# Adafruit_BME280.net
KiCad netlist of a schematic drawn in EAGLE
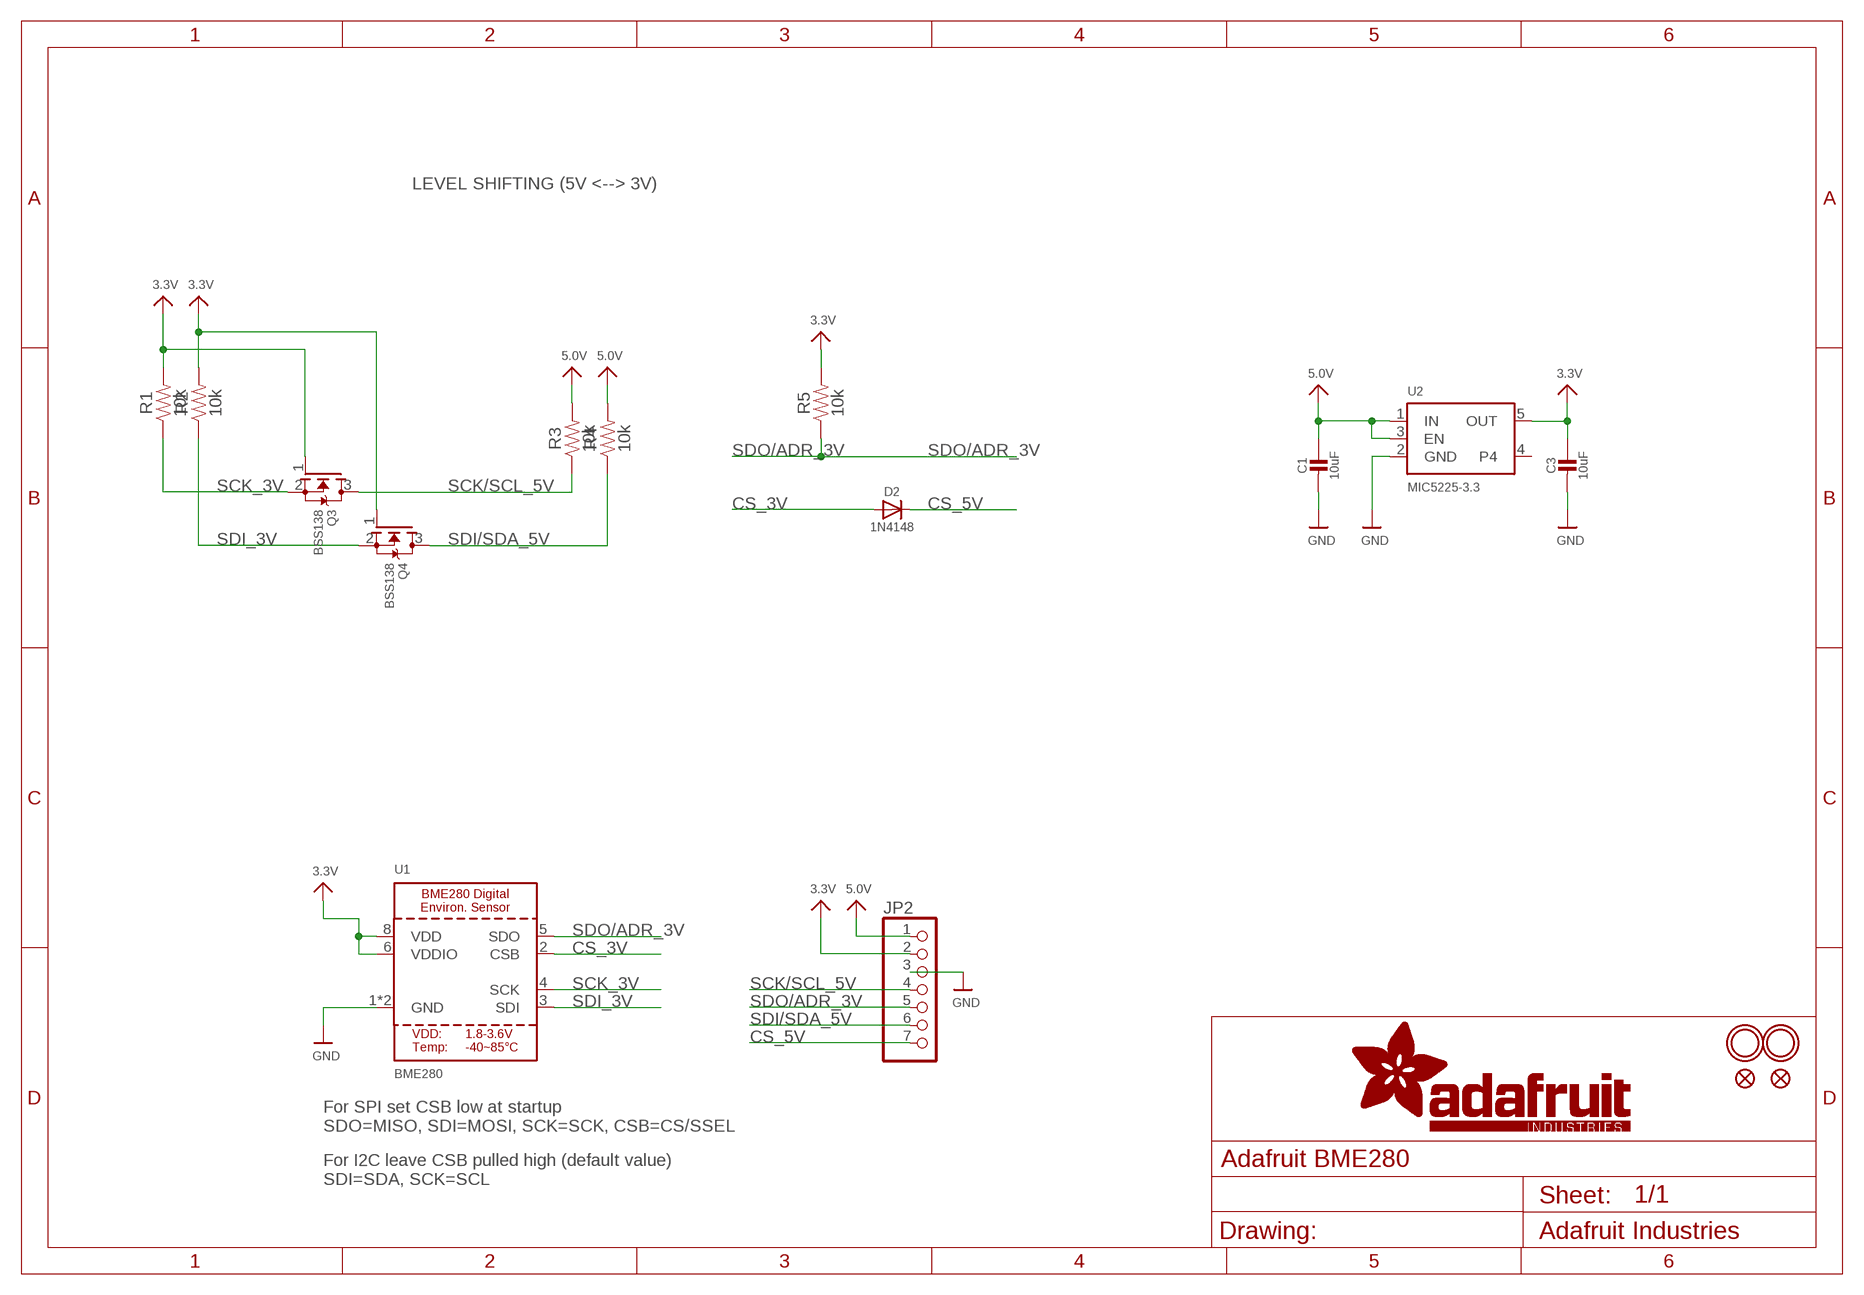
[diagram p0: schematic, sheet 1]

(export (version "E")
  (design (tool "Eeschema 10.0.6"))
  (components
    (comp (ref "C1")
      (value "10uF")
      (footprint "eagle-import:0805-NO")
      (libsource (lib "eagle-import") (part "CAP_CERAMIC0805-NOOUTLINE"))
    )
    (comp (ref "C3")
      (value "10uF")
      (footprint "eagle-import:0805-NO")
      (libsource (lib "eagle-import") (part "CAP_CERAMIC0805-NOOUTLINE"))
    )
    (comp (ref "D2")
      (value "1N4148")
      (footprint "eagle-import:SOD-323")
      (libsource (lib "eagle-import") (part "DIODESOD-323"))
    )
    (comp (ref "JP2")
      (value "HEADER-1X770MIL")
      (footprint "eagle-import:1X07_ROUND_70")
      (libsource (lib "eagle-import") (part "HEADER-1X770MIL"))
    )
    (comp (ref "Q3")
      (value "BSS138")
      (footprint "eagle-import:SOT23-WIDE")
      (libsource (lib "eagle-import") (part "MOSFET-NWIDE"))
    )
    (comp (ref "Q4")
      (value "BSS138")
      (footprint "eagle-import:SOT23-WIDE")
      (libsource (lib "eagle-import") (part "MOSFET-NWIDE"))
    )
    (comp (ref "R1")
      (value "10k")
      (footprint "eagle-import:0603")
      (libsource (lib "eagle-import") (part "10KOHM-0603-1/10W-1%"))
    )
    (comp (ref "R2")
      (value "10k")
      (footprint "eagle-import:0603")
      (libsource (lib "eagle-import") (part "10KOHM-0603-1/10W-1%"))
    )
    (comp (ref "R3")
      (value "10k")
      (footprint "eagle-import:0603")
      (libsource (lib "eagle-import") (part "10KOHM-0603-1/10W-1%"))
    )
    (comp (ref "R4")
      (value "10k")
      (footprint "eagle-import:0603")
      (libsource (lib "eagle-import") (part "10KOHM-0603-1/10W-1%"))
    )
    (comp (ref "R5")
      (value "10k")
      (footprint "eagle-import:0603")
      (libsource (lib "eagle-import") (part "10KOHM-0603-1/10W-1%"))
    )
    (comp (ref "U$5")
      (value "FIDUCIAL\"\"")
      (footprint "eagle-import:FIDUCIAL_1MM")
      (libsource (lib "eagle-import") (part "FIDUCIAL{dblquote}{dblquote}"))
    )
    (comp (ref "U$7")
      (value "MOUNTINGHOLE2.0")
      (footprint "eagle-import:MOUNTINGHOLE_2.0_PLATED")
      (libsource (lib "eagle-import") (part "MOUNTINGHOLE2.0"))
    )
    (comp (ref "U$8")
      (value "MOUNTINGHOLE2.0")
      (footprint "eagle-import:MOUNTINGHOLE_2.0_PLATED")
      (libsource (lib "eagle-import") (part "MOUNTINGHOLE2.0"))
    )
    (comp (ref "U$15")
      (value "FIDUCIAL\"\"")
      (footprint "eagle-import:FIDUCIAL_1MM")
      (libsource (lib "eagle-import") (part "FIDUCIAL{dblquote}{dblquote}"))
    )
    (comp (ref "U1")
      (value "BME280")
      (footprint "eagle-import:BME280")
      (libsource (lib "eagle-import") (part "BME280"))
    )
    (comp (ref "U2")
      (value "MIC5225-3.3")
      (footprint "eagle-import:SOT23-5")
      (libsource (lib "eagle-import") (part "VREG_SOT23-5"))
    )
  )
  (nets
    (net (code "1") (name "/CS_3V") (class "Default")
      (node (ref "D2") (pin "A") (pinfunction "A_A") (pintype "passive"))
      (node (ref "U1") (pin "2") (pinfunction "CSB_2") (pintype "input"))
    )
    (net (code "2") (name "/CS_5V") (class "Default")
      (node (ref "D2") (pin "C") (pinfunction "C_C") (pintype "passive"))
      (node (ref "JP2") (pin "7") (pinfunction "7_7") (pintype "passive"))
    )
    (net (code "3") (name "/SCK_3V") (class "Default")
      (node (ref "Q3") (pin "2") (pinfunction "S_2") (pintype "bidirectional"))
      (node (ref "R1") (pin "1") (pinfunction "1_1") (pintype "passive"))
      (node (ref "U1") (pin "4") (pinfunction "SCK_4") (pintype "input"))
    )
    (net (code "4") (name "/SCK{slash}SCL_5V") (class "Default")
      (node (ref "JP2") (pin "4") (pinfunction "4_4") (pintype "passive"))
      (node (ref "Q3") (pin "3") (pinfunction "D_3") (pintype "bidirectional"))
      (node (ref "R3") (pin "1") (pinfunction "1_1") (pintype "passive"))
    )
    (net (code "5") (name "/SDI_3V") (class "Default")
      (node (ref "Q4") (pin "2") (pinfunction "S_2") (pintype "bidirectional"))
      (node (ref "R2") (pin "1") (pinfunction "1_1") (pintype "passive"))
      (node (ref "U1") (pin "3") (pinfunction "SDI_3") (pintype "input"))
    )
    (net (code "6") (name "/SDI{slash}SDA_5V") (class "Default")
      (node (ref "JP2") (pin "6") (pinfunction "6_6") (pintype "passive"))
      (node (ref "Q4") (pin "3") (pinfunction "D_3") (pintype "bidirectional"))
      (node (ref "R4") (pin "1") (pinfunction "1_1") (pintype "passive"))
    )
    (net (code "7") (name "/SDO{slash}ADR_3V") (class "Default")
      (node (ref "JP2") (pin "5") (pinfunction "5_5") (pintype "passive"))
      (node (ref "R5") (pin "1") (pinfunction "1_1") (pintype "passive"))
      (node (ref "U1") (pin "5") (pinfunction "SDO_5") (pintype "output"))
    )
    (net (code "8") (name "3.3V") (class "Default")
      (node (ref "C3") (pin "1") (pinfunction "1_1") (pintype "passive"))
      (node (ref "JP2") (pin "2") (pinfunction "2_2") (pintype "passive"))
      (node (ref "Q3") (pin "1") (pinfunction "G_1") (pintype "bidirectional"))
      (node (ref "Q4") (pin "1") (pinfunction "G_1") (pintype "bidirectional"))
      (node (ref "R1") (pin "2") (pinfunction "2_2") (pintype "passive"))
      (node (ref "R2") (pin "2") (pinfunction "2_2") (pintype "passive"))
      (node (ref "R5") (pin "2") (pinfunction "2_2") (pintype "passive"))
      (node (ref "U1") (pin "6") (pinfunction "VDDIO_6") (pintype "power_in"))
      (node (ref "U1") (pin "8") (pinfunction "VDD_8") (pintype "power_in"))
      (node (ref "U2") (pin "5") (pinfunction "OUT_5") (pintype "power_in"))
    )
    (net (code "9") (name "5.0V") (class "Default")
      (node (ref "C1") (pin "1") (pinfunction "1_1") (pintype "passive"))
      (node (ref "JP2") (pin "1") (pinfunction "1_1") (pintype "passive"))
      (node (ref "R3") (pin "2") (pinfunction "2_2") (pintype "passive"))
      (node (ref "R4") (pin "2") (pinfunction "2_2") (pintype "passive"))
      (node (ref "U2") (pin "1") (pinfunction "IN_1") (pintype "power_in"))
      (node (ref "U2") (pin "3") (pinfunction "EN_3") (pintype "input"))
    )
    (net (code "10") (name "GND") (class "Default")
      (node (ref "C1") (pin "2") (pinfunction "2_2") (pintype "passive"))
      (node (ref "C3") (pin "2") (pinfunction "2_2") (pintype "passive"))
      (node (ref "JP2") (pin "3") (pinfunction "3_3") (pintype "passive"))
      (node (ref "U1") (pin "1") (pinfunction "GND_1") (pintype "power_in"))
      (node (ref "U1") (pin "7") (pinfunction "GND_7") (pintype "power_in"))
      (node (ref "U2") (pin "2") (pinfunction "GND_2") (pintype "power_in"))
    )
    (net (code "11") (name "unconnected-(U2-P4-Pad4)") (class "Default")
      (node (ref "U2") (pin "4") (pinfunction "P4_4") (pintype "bidirectional"))
    )
  )
)
